# irkit_v03.net
KiCad netlist of a schematic drawn in EAGLE
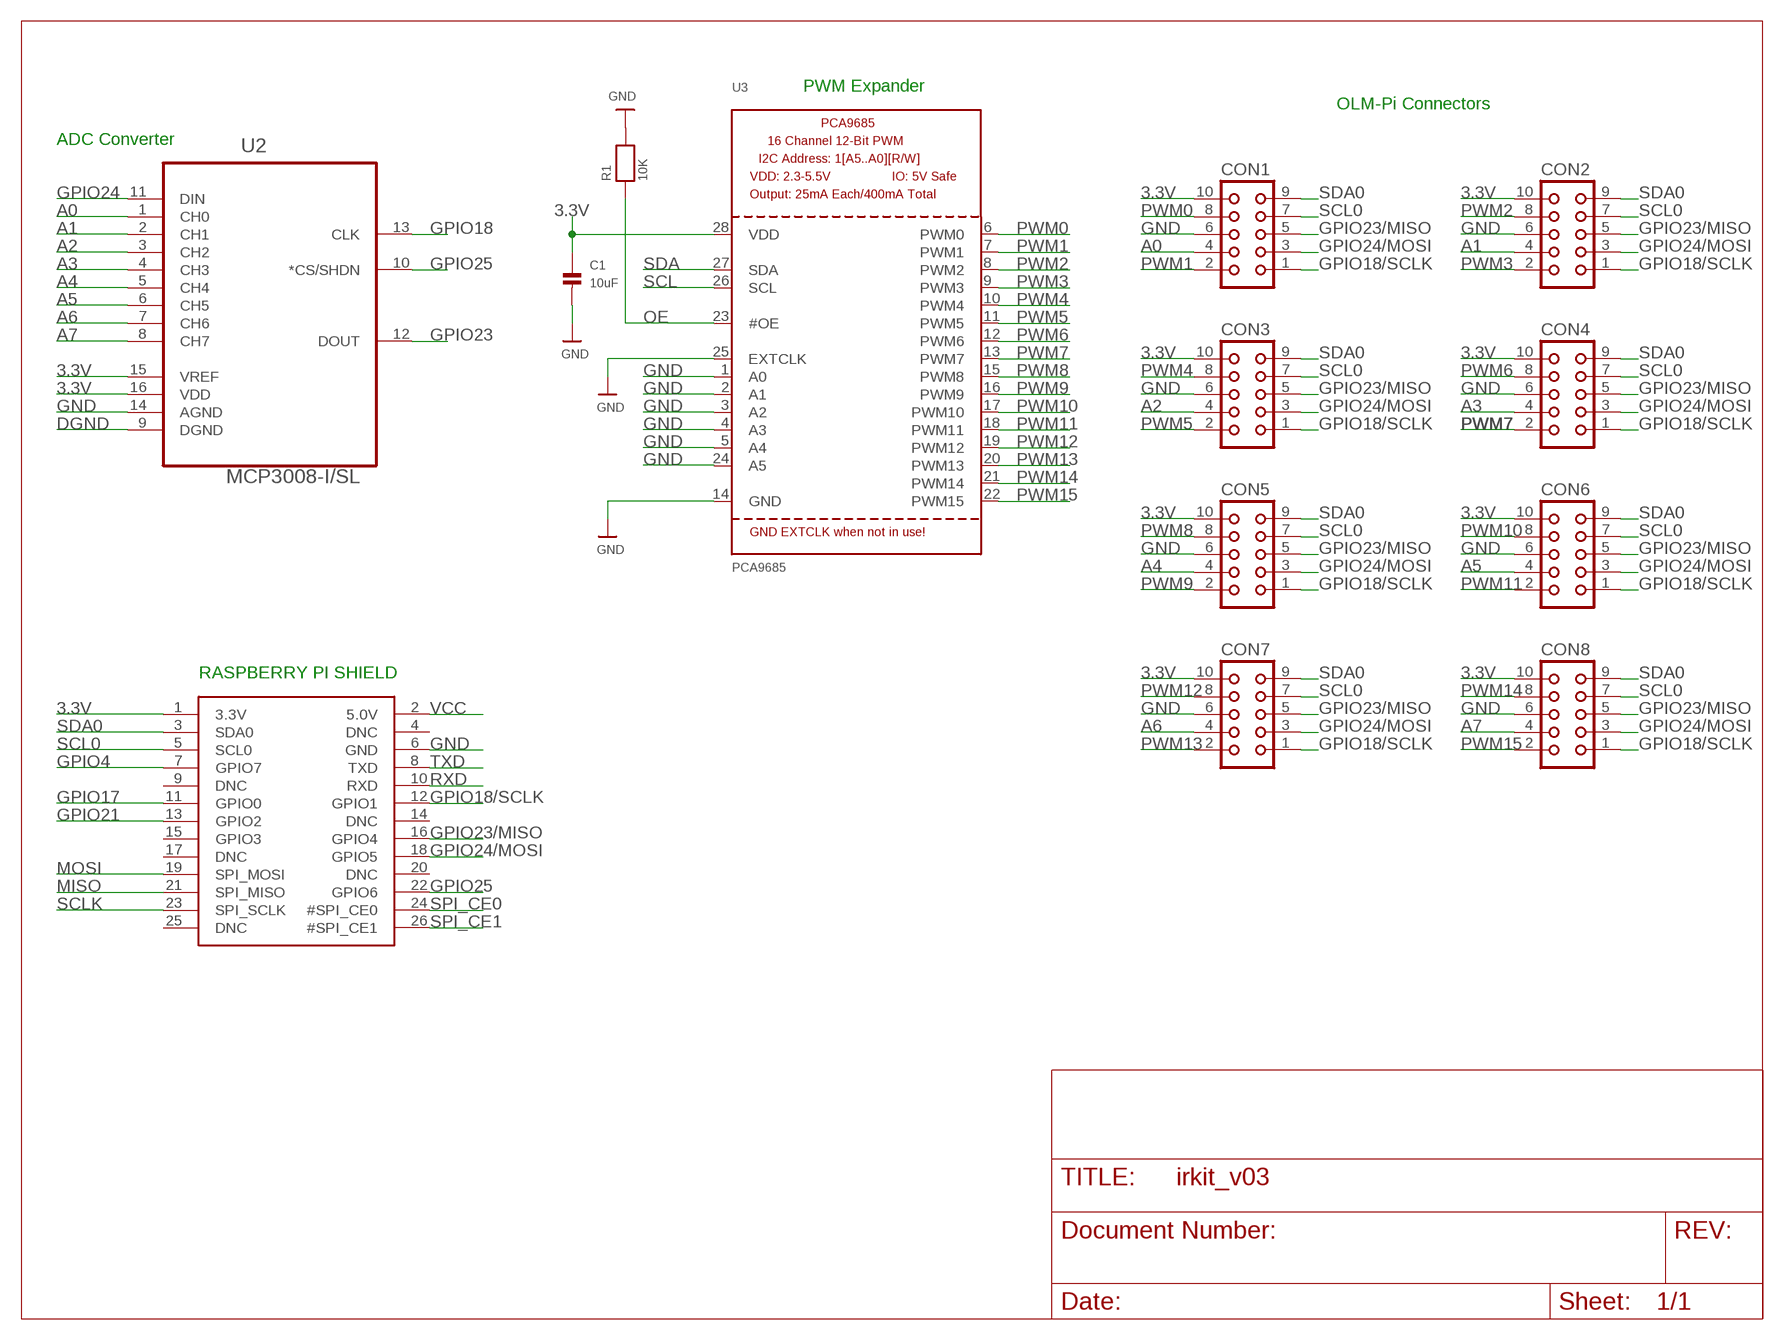
[diagram p0: schematic, sheet 1]

(export (version "E")
  (design (tool "Eeschema 10.0.6"))
  (components
    (comp (ref "C1")
      (value "10uF")
      (footprint "eagle-import:0805")
      (libsource (lib "eagle-import") (part "CAP_CERAMIC0805"))
    )
    (comp (ref "CON1")
      (value "CON10L")
      (footprint "eagle-import:CON10L")
      (libsource (lib "eagle-import") (part "CON10L"))
    )
    (comp (ref "CON2")
      (value "CON10L")
      (footprint "eagle-import:CON10L")
      (libsource (lib "eagle-import") (part "CON10L"))
    )
    (comp (ref "CON3")
      (value "CON10L")
      (footprint "eagle-import:CON10L")
      (libsource (lib "eagle-import") (part "CON10L"))
    )
    (comp (ref "CON4")
      (value "CON10L")
      (footprint "eagle-import:CON10L")
      (libsource (lib "eagle-import") (part "CON10L"))
    )
    (comp (ref "CON5")
      (value "CON10L")
      (footprint "eagle-import:CON10L")
      (libsource (lib "eagle-import") (part "CON10L"))
    )
    (comp (ref "CON6")
      (value "CON10L")
      (footprint "eagle-import:CON10L")
      (libsource (lib "eagle-import") (part "CON10L"))
    )
    (comp (ref "CON7")
      (value "CON10L")
      (footprint "eagle-import:CON10L")
      (libsource (lib "eagle-import") (part "CON10L"))
    )
    (comp (ref "CON8")
      (value "CON10L")
      (footprint "eagle-import:CON10L")
      (libsource (lib "eagle-import") (part "CON10L"))
    )
    (comp (ref "R1")
      (value "10K")
      (footprint "eagle-import:0805")
      (libsource (lib "eagle-import") (part "RESISTOR0805"))
    )
    (comp (ref "U$1")
      (value "RASPBERRYPI_BB")
      (footprint "eagle-import:RASBERRYPI_SHIELD")
      (libsource (lib "eagle-import") (part "RASPBERRYPI_BB"))
    )
    (comp (ref "U2")
      (value "MCP3008-I/SL")
      (footprint "eagle-import:SOIC127P600X175-16N")
      (libsource (lib "eagle-import") (part "MCP3008-I/SL"))
    )
    (comp (ref "U3")
      (value "PCA9685")
      (footprint "eagle-import:TSSOP28")
      (libsource (lib "eagle-import") (part "PCA9685"))
    )
  )
  (nets
    (net (code "1") (name "/3.3V") (class "Default")
      (node (ref "C1") (pin "1") (pinfunction "P$1_1") (pintype "passive"))
      (node (ref "CON1") (pin "10") (pinfunction "10_10") (pintype "passive"))
      (node (ref "CON2") (pin "10") (pinfunction "10_10") (pintype "passive"))
      (node (ref "CON3") (pin "10") (pinfunction "10_10") (pintype "passive"))
      (node (ref "CON4") (pin "10") (pinfunction "10_10") (pintype "passive"))
      (node (ref "CON5") (pin "10") (pinfunction "10_10") (pintype "passive"))
      (node (ref "CON6") (pin "10") (pinfunction "10_10") (pintype "passive"))
      (node (ref "CON7") (pin "10") (pinfunction "10_10") (pintype "passive"))
      (node (ref "CON8") (pin "10") (pinfunction "10_10") (pintype "passive"))
      (node (ref "U$1") (pin "1") (pinfunction "3.3V_1") (pintype "power_in"))
      (node (ref "U2") (pin "15") (pinfunction "VREF_15") (pintype "input"))
      (node (ref "U2") (pin "16") (pinfunction "VDD_16") (pintype "power_in"))
      (node (ref "U3") (pin "28") (pinfunction "VDD_28") (pintype "power_in"))
    )
    (net (code "2") (name "/A0") (class "Default")
      (node (ref "CON1") (pin "4") (pinfunction "4_4") (pintype "passive"))
      (node (ref "U2") (pin "1") (pinfunction "CH0_1") (pintype "input"))
    )
    (net (code "3") (name "/A1") (class "Default")
      (node (ref "CON2") (pin "4") (pinfunction "4_4") (pintype "passive"))
      (node (ref "U2") (pin "2") (pinfunction "CH1_2") (pintype "input"))
    )
    (net (code "4") (name "/A2") (class "Default")
      (node (ref "CON3") (pin "4") (pinfunction "4_4") (pintype "passive"))
      (node (ref "U2") (pin "3") (pinfunction "CH2_3") (pintype "input"))
    )
    (net (code "5") (name "/A3") (class "Default")
      (node (ref "CON4") (pin "4") (pinfunction "4_4") (pintype "passive"))
      (node (ref "U2") (pin "4") (pinfunction "CH3_4") (pintype "input"))
    )
    (net (code "6") (name "/A4") (class "Default")
      (node (ref "CON5") (pin "4") (pinfunction "4_4") (pintype "passive"))
      (node (ref "U2") (pin "5") (pinfunction "CH4_5") (pintype "input"))
    )
    (net (code "7") (name "/A5") (class "Default")
      (node (ref "CON6") (pin "4") (pinfunction "4_4") (pintype "passive"))
      (node (ref "U2") (pin "6") (pinfunction "CH5_6") (pintype "input"))
    )
    (net (code "8") (name "/A6") (class "Default")
      (node (ref "CON7") (pin "4") (pinfunction "4_4") (pintype "passive"))
      (node (ref "U2") (pin "7") (pinfunction "CH6_7") (pintype "input"))
    )
    (net (code "9") (name "/A7") (class "Default")
      (node (ref "CON8") (pin "4") (pinfunction "4_4") (pintype "passive"))
      (node (ref "U2") (pin "8") (pinfunction "CH7_8") (pintype "input"))
    )
    (net (code "10") (name "/DGND") (class "Default")
      (node (ref "U2") (pin "9") (pinfunction "DGND_9") (pintype "passive"))
    )
    (net (code "11") (name "/GPIO4") (class "Default")
      (node (ref "U$1") (pin "7") (pinfunction "GPIO7_7") (pintype "bidirectional"))
    )
    (net (code "12") (name "/GPIO17") (class "Default")
      (node (ref "U$1") (pin "11") (pinfunction "GPIO0_11") (pintype "bidirectional"))
    )
    (net (code "13") (name "/GPIO18") (class "Default")
      (node (ref "U2") (pin "13") (pinfunction "CLK_13") (pintype "input"))
    )
    (net (code "14") (name "/GPIO18{slash}SCLK") (class "Default")
      (node (ref "CON1") (pin "1") (pinfunction "1_1") (pintype "passive"))
      (node (ref "CON2") (pin "1") (pinfunction "1_1") (pintype "passive"))
      (node (ref "CON3") (pin "1") (pinfunction "1_1") (pintype "passive"))
      (node (ref "CON4") (pin "1") (pinfunction "1_1") (pintype "passive"))
      (node (ref "CON5") (pin "1") (pinfunction "1_1") (pintype "passive"))
      (node (ref "CON6") (pin "1") (pinfunction "1_1") (pintype "passive"))
      (node (ref "CON7") (pin "1") (pinfunction "1_1") (pintype "passive"))
      (node (ref "CON8") (pin "1") (pinfunction "1_1") (pintype "passive"))
      (node (ref "U$1") (pin "12") (pinfunction "GPIO1_12") (pintype "bidirectional"))
    )
    (net (code "15") (name "/GPIO21") (class "Default")
      (node (ref "U$1") (pin "13") (pinfunction "GPIO2_13") (pintype "bidirectional"))
    )
    (net (code "16") (name "/GPIO23") (class "Default")
      (node (ref "U2") (pin "12") (pinfunction "DOUT_12") (pintype "output"))
    )
    (net (code "17") (name "/GPIO23{slash}MISO") (class "Default")
      (node (ref "CON1") (pin "5") (pinfunction "5_5") (pintype "passive"))
      (node (ref "CON2") (pin "5") (pinfunction "5_5") (pintype "passive"))
      (node (ref "CON3") (pin "5") (pinfunction "5_5") (pintype "passive"))
      (node (ref "CON4") (pin "5") (pinfunction "5_5") (pintype "passive"))
      (node (ref "CON5") (pin "5") (pinfunction "5_5") (pintype "passive"))
      (node (ref "CON6") (pin "5") (pinfunction "5_5") (pintype "passive"))
      (node (ref "CON7") (pin "5") (pinfunction "5_5") (pintype "passive"))
      (node (ref "CON8") (pin "5") (pinfunction "5_5") (pintype "passive"))
      (node (ref "U$1") (pin "16") (pinfunction "GPIO4_16") (pintype "bidirectional"))
    )
    (net (code "18") (name "/GPIO24") (class "Default")
      (node (ref "U2") (pin "11") (pinfunction "DIN_11") (pintype "input"))
    )
    (net (code "19") (name "/GPIO24{slash}MOSI") (class "Default")
      (node (ref "CON1") (pin "3") (pinfunction "3_3") (pintype "passive"))
      (node (ref "CON2") (pin "3") (pinfunction "3_3") (pintype "passive"))
      (node (ref "CON3") (pin "3") (pinfunction "3_3") (pintype "passive"))
      (node (ref "CON4") (pin "3") (pinfunction "3_3") (pintype "passive"))
      (node (ref "CON5") (pin "3") (pinfunction "3_3") (pintype "passive"))
      (node (ref "CON6") (pin "3") (pinfunction "3_3") (pintype "passive"))
      (node (ref "CON7") (pin "3") (pinfunction "3_3") (pintype "passive"))
      (node (ref "CON8") (pin "3") (pinfunction "3_3") (pintype "passive"))
      (node (ref "U$1") (pin "18") (pinfunction "GPIO5_18") (pintype "bidirectional"))
    )
    (net (code "20") (name "/GPIO25") (class "Default")
      (node (ref "U$1") (pin "22") (pinfunction "GPIO6_22") (pintype "bidirectional"))
      (node (ref "U2") (pin "10") (pinfunction "*CS/SHDN_10") (pintype "input"))
    )
    (net (code "21") (name "/MISO") (class "Default")
      (node (ref "U$1") (pin "21") (pinfunction "SPI_MISO_21") (pintype "input"))
    )
    (net (code "22") (name "/MOSI") (class "Default")
      (node (ref "U$1") (pin "19") (pinfunction "SPI_MOSI_19") (pintype "output"))
    )
    (net (code "23") (name "/OE") (class "Default")
      (node (ref "R1") (pin "1") (pinfunction "1_1") (pintype "passive"))
      (node (ref "U3") (pin "23") (pinfunction "#OE_23") (pintype "input"))
    )
    (net (code "24") (name "/PWM0") (class "Default")
      (node (ref "CON1") (pin "8") (pinfunction "8_8") (pintype "passive"))
      (node (ref "U3") (pin "6") (pinfunction "PWM0_6") (pintype "output"))
    )
    (net (code "25") (name "/PWM1") (class "Default")
      (node (ref "CON1") (pin "2") (pinfunction "2_2") (pintype "passive"))
      (node (ref "U3") (pin "7") (pinfunction "PWM1_7") (pintype "output"))
    )
    (net (code "26") (name "/PWM2") (class "Default")
      (node (ref "CON2") (pin "8") (pinfunction "8_8") (pintype "passive"))
      (node (ref "U3") (pin "8") (pinfunction "PWM2_8") (pintype "output"))
    )
    (net (code "27") (name "/PWM3") (class "Default")
      (node (ref "CON2") (pin "2") (pinfunction "2_2") (pintype "passive"))
      (node (ref "U3") (pin "9") (pinfunction "PWM3_9") (pintype "output"))
    )
    (net (code "28") (name "/PWM4") (class "Default")
      (node (ref "CON3") (pin "8") (pinfunction "8_8") (pintype "passive"))
      (node (ref "U3") (pin "10") (pinfunction "PWM4_10") (pintype "output"))
    )
    (net (code "29") (name "/PWM5") (class "Default")
      (node (ref "CON3") (pin "2") (pinfunction "2_2") (pintype "passive"))
      (node (ref "U3") (pin "11") (pinfunction "PWM5_11") (pintype "output"))
    )
    (net (code "30") (name "/PWM6") (class "Default")
      (node (ref "CON4") (pin "8") (pinfunction "8_8") (pintype "passive"))
      (node (ref "U3") (pin "12") (pinfunction "PWM6_12") (pintype "output"))
    )
    (net (code "31") (name "/PWM7") (class "Default")
      (node (ref "CON4") (pin "2") (pinfunction "2_2") (pintype "passive"))
      (node (ref "U3") (pin "13") (pinfunction "PWM7_13") (pintype "output"))
    )
    (net (code "32") (name "/PWM8") (class "Default")
      (node (ref "CON5") (pin "8") (pinfunction "8_8") (pintype "passive"))
      (node (ref "U3") (pin "15") (pinfunction "PWM8_15") (pintype "output"))
    )
    (net (code "33") (name "/PWM9") (class "Default")
      (node (ref "CON5") (pin "2") (pinfunction "2_2") (pintype "passive"))
      (node (ref "U3") (pin "16") (pinfunction "PWM9_16") (pintype "output"))
    )
    (net (code "34") (name "/PWM10") (class "Default")
      (node (ref "CON6") (pin "8") (pinfunction "8_8") (pintype "passive"))
      (node (ref "U3") (pin "17") (pinfunction "PWM10_17") (pintype "output"))
    )
    (net (code "35") (name "/PWM11") (class "Default")
      (node (ref "CON6") (pin "2") (pinfunction "2_2") (pintype "passive"))
      (node (ref "U3") (pin "18") (pinfunction "PWM11_18") (pintype "output"))
    )
    (net (code "36") (name "/PWM12") (class "Default")
      (node (ref "CON7") (pin "8") (pinfunction "8_8") (pintype "passive"))
      (node (ref "U3") (pin "19") (pinfunction "PWM12_19") (pintype "output"))
    )
    (net (code "37") (name "/PWM13") (class "Default")
      (node (ref "CON7") (pin "2") (pinfunction "2_2") (pintype "passive"))
      (node (ref "U3") (pin "20") (pinfunction "PWM13_20") (pintype "output"))
    )
    (net (code "38") (name "/PWM14") (class "Default")
      (node (ref "CON8") (pin "8") (pinfunction "8_8") (pintype "passive"))
      (node (ref "U3") (pin "21") (pinfunction "PWM14_21") (pintype "output"))
    )
    (net (code "39") (name "/PWM15") (class "Default")
      (node (ref "CON8") (pin "2") (pinfunction "2_2") (pintype "passive"))
      (node (ref "U3") (pin "22") (pinfunction "PWM15_22") (pintype "output"))
    )
    (net (code "40") (name "/RXD") (class "Default")
      (node (ref "U$1") (pin "10") (pinfunction "RXD_10") (pintype "input"))
    )
    (net (code "41") (name "/SCL") (class "Default")
      (node (ref "U3") (pin "26") (pinfunction "SCL_26") (pintype "bidirectional"))
    )
    (net (code "42") (name "/SCL0") (class "Default")
      (node (ref "CON1") (pin "7") (pinfunction "7_7") (pintype "passive"))
      (node (ref "CON2") (pin "7") (pinfunction "7_7") (pintype "passive"))
      (node (ref "CON3") (pin "7") (pinfunction "7_7") (pintype "passive"))
      (node (ref "CON4") (pin "7") (pinfunction "7_7") (pintype "passive"))
      (node (ref "CON5") (pin "7") (pinfunction "7_7") (pintype "passive"))
      (node (ref "CON6") (pin "7") (pinfunction "7_7") (pintype "passive"))
      (node (ref "CON7") (pin "7") (pinfunction "7_7") (pintype "passive"))
      (node (ref "CON8") (pin "7") (pinfunction "7_7") (pintype "passive"))
      (node (ref "U$1") (pin "5") (pinfunction "SCL0_5") (pintype "output"))
    )
    (net (code "43") (name "/SCLK") (class "Default")
      (node (ref "U$1") (pin "23") (pinfunction "SPI_SCLK_23") (pintype "output"))
    )
    (net (code "44") (name "/SDA") (class "Default")
      (node (ref "U3") (pin "27") (pinfunction "SDA_27") (pintype "bidirectional"))
    )
    (net (code "45") (name "/SDA0") (class "Default")
      (node (ref "CON1") (pin "9") (pinfunction "9_9") (pintype "passive"))
      (node (ref "CON2") (pin "9") (pinfunction "9_9") (pintype "passive"))
      (node (ref "CON3") (pin "9") (pinfunction "9_9") (pintype "passive"))
      (node (ref "CON4") (pin "9") (pinfunction "9_9") (pintype "passive"))
      (node (ref "CON5") (pin "9") (pinfunction "9_9") (pintype "passive"))
      (node (ref "CON6") (pin "9") (pinfunction "9_9") (pintype "passive"))
      (node (ref "CON7") (pin "9") (pinfunction "9_9") (pintype "passive"))
      (node (ref "CON8") (pin "9") (pinfunction "9_9") (pintype "passive"))
      (node (ref "U$1") (pin "3") (pinfunction "SDA0_3") (pintype "bidirectional"))
    )
    (net (code "46") (name "/SPI_CE0") (class "Default")
      (node (ref "U$1") (pin "24") (pinfunction "#SPI_CE0_24") (pintype "output"))
    )
    (net (code "47") (name "/SPI_CE1") (class "Default")
      (node (ref "U$1") (pin "26") (pinfunction "#SPI_CE1_26") (pintype "output"))
    )
    (net (code "48") (name "/TXD") (class "Default")
      (node (ref "U$1") (pin "8") (pinfunction "TXD_8") (pintype "output"))
    )
    (net (code "49") (name "/VCC") (class "Default")
      (node (ref "U$1") (pin "2") (pinfunction "5.0V_2") (pintype "power_in"))
    )
    (net (code "50") (name "GND") (class "Default")
      (node (ref "C1") (pin "2") (pinfunction "P$2_2") (pintype "passive"))
      (node (ref "CON1") (pin "6") (pinfunction "6_6") (pintype "passive"))
      (node (ref "CON2") (pin "6") (pinfunction "6_6") (pintype "passive"))
      (node (ref "CON3") (pin "6") (pinfunction "6_6") (pintype "passive"))
      (node (ref "CON4") (pin "6") (pinfunction "6_6") (pintype "passive"))
      (node (ref "CON5") (pin "6") (pinfunction "6_6") (pintype "passive"))
      (node (ref "CON6") (pin "6") (pinfunction "6_6") (pintype "passive"))
      (node (ref "CON7") (pin "6") (pinfunction "6_6") (pintype "passive"))
      (node (ref "CON8") (pin "6") (pinfunction "6_6") (pintype "passive"))
      (node (ref "R1") (pin "2") (pinfunction "2_2") (pintype "passive"))
      (node (ref "U$1") (pin "6") (pinfunction "GND_6") (pintype "power_in"))
      (node (ref "U2") (pin "14") (pinfunction "AGND_14") (pintype "passive"))
      (node (ref "U3") (pin "1") (pinfunction "A0_1") (pintype "bidirectional"))
      (node (ref "U3") (pin "14") (pinfunction "GND_14") (pintype "power_in"))
      (node (ref "U3") (pin "2") (pinfunction "A1_2") (pintype "bidirectional"))
      (node (ref "U3") (pin "24") (pinfunction "A5_24") (pintype "bidirectional"))
      (node (ref "U3") (pin "25") (pinfunction "EXTCLK_25") (pintype "input"))
      (node (ref "U3") (pin "3") (pinfunction "A2_3") (pintype "bidirectional"))
      (node (ref "U3") (pin "4") (pinfunction "A3_4") (pintype "bidirectional"))
      (node (ref "U3") (pin "5") (pinfunction "A4_5") (pintype "bidirectional"))
    )
    (net (code "51") (name "unconnected-(U$1-DNC-Pad4)") (class "Default")
      (node (ref "U$1") (pin "4") (pinfunction "DNC_4") (pintype "no_connect"))
    )
    (net (code "52") (name "unconnected-(U$1-DNC-Pad9)") (class "Default")
      (node (ref "U$1") (pin "9") (pinfunction "DNC_9") (pintype "no_connect"))
    )
    (net (code "53") (name "unconnected-(U$1-DNC-Pad14)") (class "Default")
      (node (ref "U$1") (pin "14") (pinfunction "DNC_14") (pintype "no_connect"))
    )
    (net (code "54") (name "unconnected-(U$1-DNC-Pad17)") (class "Default")
      (node (ref "U$1") (pin "17") (pinfunction "DNC_17") (pintype "no_connect"))
    )
    (net (code "55") (name "unconnected-(U$1-DNC-Pad20)") (class "Default")
      (node (ref "U$1") (pin "20") (pinfunction "DNC_20") (pintype "no_connect"))
    )
    (net (code "56") (name "unconnected-(U$1-DNC-Pad25)") (class "Default")
      (node (ref "U$1") (pin "25") (pinfunction "DNC_25") (pintype "no_connect"))
    )
    (net (code "57") (name "unconnected-(U$1-GPIO3-Pad15)") (class "Default")
      (node (ref "U$1") (pin "15") (pinfunction "GPIO3_15") (pintype "bidirectional"))
    )
  )
)
